# TT7B_v1_0.net
KiCad netlist of a schematic drawn in EAGLE
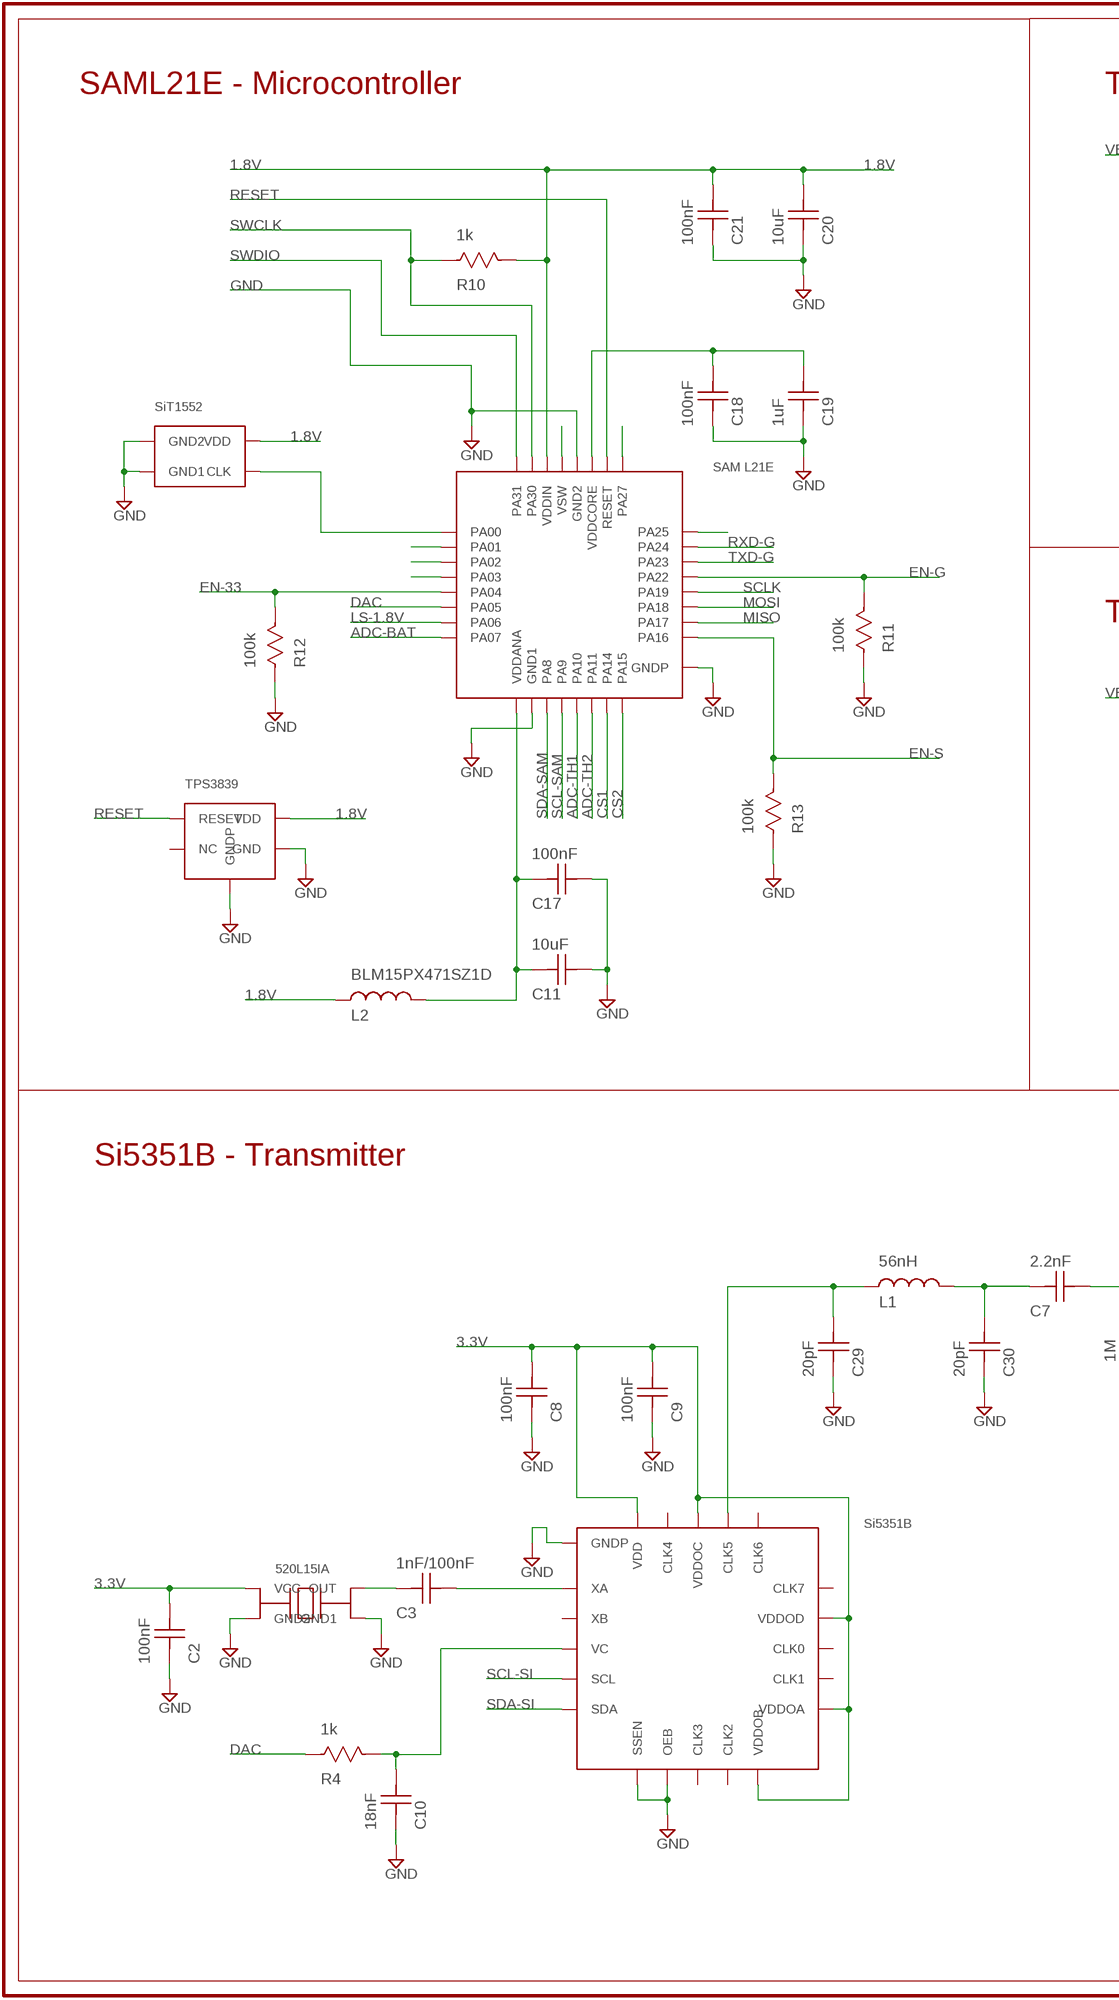
[diagram p0: schematic, sheet 1, part 1 of 2]
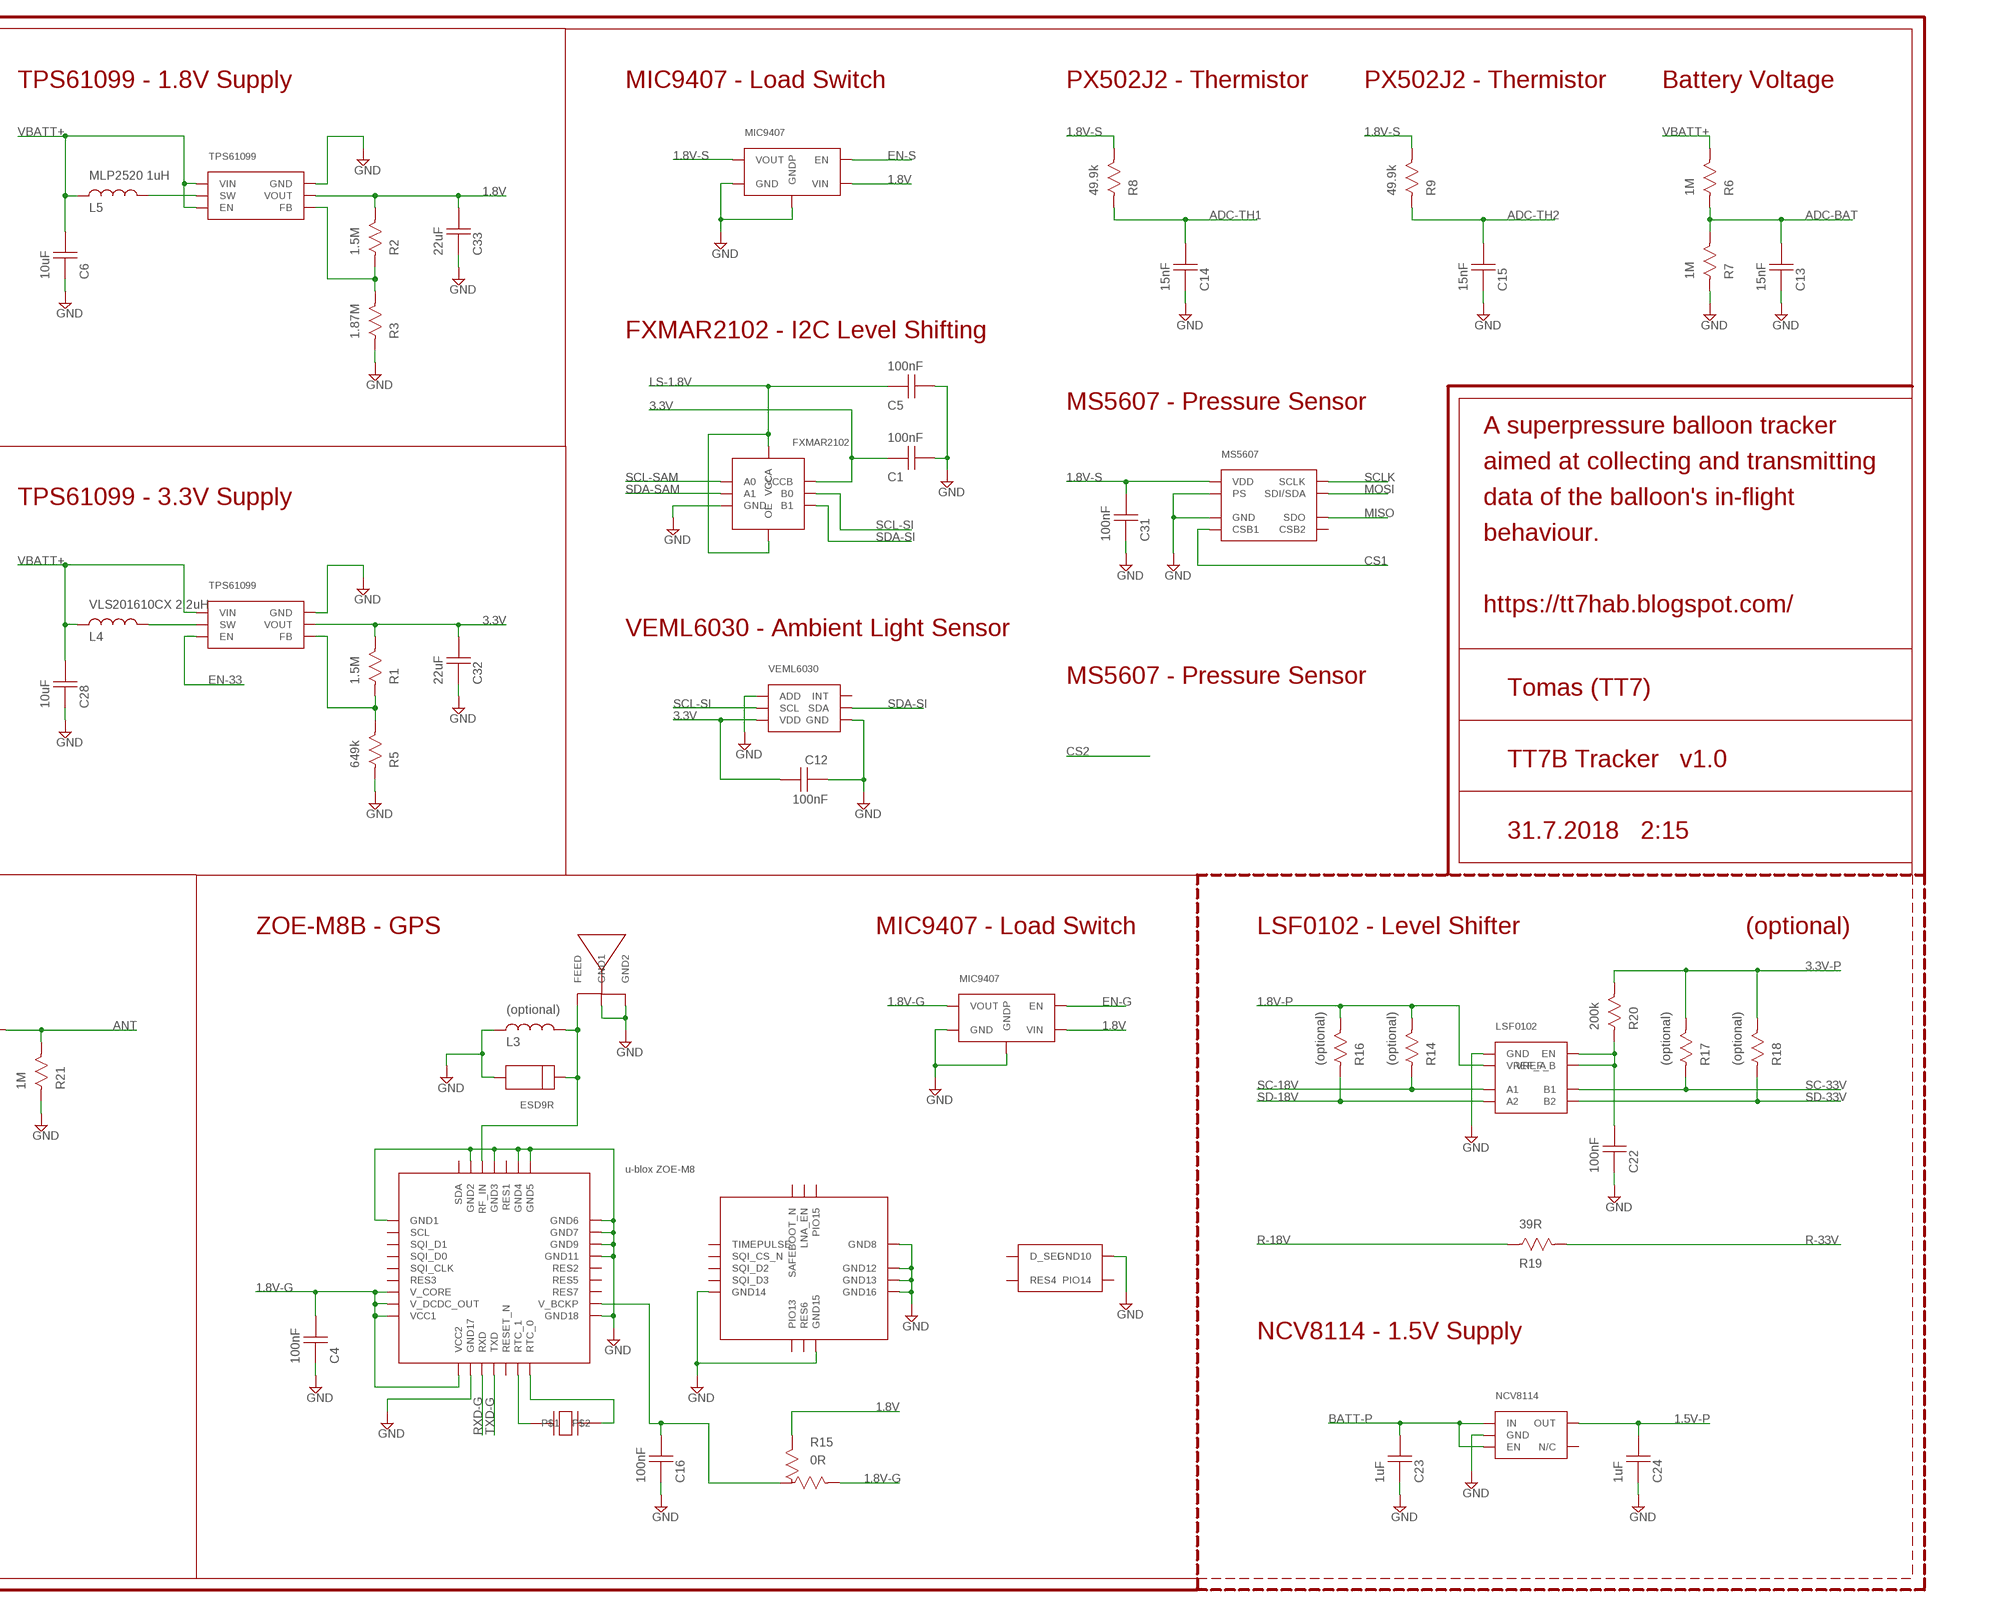
[diagram p1: schematic, sheet 1, part 2 of 2]

(export (version "E")
  (design (tool "Eeschema 10.0.6"))
  (components
    (comp (ref "C1")
      (value "100nF")
      (footprint "eagle-import:CAP0402")
      (libsource (lib "eagle-import") (part "CAP0402"))
    )
    (comp (ref "C2")
      (value "100nF")
      (footprint "eagle-import:CAP0402")
      (libsource (lib "eagle-import") (part "CAP0402"))
    )
    (comp (ref "C3")
      (value "1nF/100nF")
      (footprint "eagle-import:CAP0402")
      (libsource (lib "eagle-import") (part "CAP0402"))
    )
    (comp (ref "C4")
      (value "100nF")
      (footprint "eagle-import:CAP0402")
      (libsource (lib "eagle-import") (part "CAP0402"))
    )
    (comp (ref "C5")
      (value "100nF")
      (footprint "eagle-import:CAP0402")
      (libsource (lib "eagle-import") (part "CAP0402"))
    )
    (comp (ref "C6")
      (value "10uF")
      (footprint "eagle-import:CAP0402")
      (libsource (lib "eagle-import") (part "CAP0402"))
    )
    (comp (ref "C7")
      (value "2.2nF")
      (footprint "eagle-import:CAP0402")
      (libsource (lib "eagle-import") (part "CAP0402"))
    )
    (comp (ref "C8")
      (value "100nF")
      (footprint "eagle-import:CAP0402")
      (libsource (lib "eagle-import") (part "CAP0402"))
    )
    (comp (ref "C9")
      (value "100nF")
      (footprint "eagle-import:CAP0402")
      (libsource (lib "eagle-import") (part "CAP0402"))
    )
    (comp (ref "C10")
      (value "18nF")
      (footprint "eagle-import:CAP0402")
      (libsource (lib "eagle-import") (part "CAP0402"))
    )
    (comp (ref "C11")
      (value "10uF")
      (footprint "eagle-import:CAP0402")
      (libsource (lib "eagle-import") (part "CAP0402"))
    )
    (comp (ref "C12")
      (value "100nF")
      (footprint "eagle-import:CAP0402")
      (libsource (lib "eagle-import") (part "CAP0402"))
    )
    (comp (ref "C13")
      (value "15nF")
      (footprint "eagle-import:CAP0402")
      (libsource (lib "eagle-import") (part "CAP0402"))
    )
    (comp (ref "C14")
      (value "15nF")
      (footprint "eagle-import:CAP0402")
      (libsource (lib "eagle-import") (part "CAP0402"))
    )
    (comp (ref "C15")
      (value "15nF")
      (footprint "eagle-import:CAP0402")
      (libsource (lib "eagle-import") (part "CAP0402"))
    )
    (comp (ref "C16")
      (value "100nF")
      (footprint "eagle-import:CAP0402")
      (libsource (lib "eagle-import") (part "CAP0402"))
    )
    (comp (ref "C17")
      (value "100nF")
      (footprint "eagle-import:CAP0402")
      (libsource (lib "eagle-import") (part "CAP0402"))
    )
    (comp (ref "C18")
      (value "100nF")
      (footprint "eagle-import:CAP0402")
      (libsource (lib "eagle-import") (part "CAP0402"))
    )
    (comp (ref "C19")
      (value "1uF")
      (footprint "eagle-import:CAP0402")
      (libsource (lib "eagle-import") (part "CAP0402"))
    )
    (comp (ref "C20")
      (value "10uF")
      (footprint "eagle-import:CAP0402")
      (libsource (lib "eagle-import") (part "CAP0402"))
    )
    (comp (ref "C21")
      (value "100nF")
      (footprint "eagle-import:CAP0402")
      (libsource (lib "eagle-import") (part "CAP0402"))
    )
    (comp (ref "C22")
      (value "100nF")
      (footprint "eagle-import:CAP0402")
      (libsource (lib "eagle-import") (part "CAP0402"))
    )
    (comp (ref "C23")
      (value "1uF")
      (footprint "eagle-import:CAP0402")
      (libsource (lib "eagle-import") (part "CAP0402"))
    )
    (comp (ref "C24")
      (value "1uF")
      (footprint "eagle-import:CAP0402")
      (libsource (lib "eagle-import") (part "CAP0402"))
    )
    (comp (ref "C28")
      (value "10uF")
      (footprint "eagle-import:CAP0402")
      (libsource (lib "eagle-import") (part "CAP0402"))
    )
    (comp (ref "C29")
      (value "20pF")
      (footprint "eagle-import:CAP0402")
      (libsource (lib "eagle-import") (part "CAP0402"))
    )
    (comp (ref "C30")
      (value "20pF")
      (footprint "eagle-import:CAP0402")
      (libsource (lib "eagle-import") (part "CAP0402"))
    )
    (comp (ref "C31")
      (value "100nF")
      (footprint "eagle-import:CAP0402")
      (libsource (lib "eagle-import") (part "CAP0402"))
    )
    (comp (ref "C32")
      (value "22uF")
      (footprint "eagle-import:CAP0603")
      (libsource (lib "eagle-import") (part "CAP0603"))
    )
    (comp (ref "C33")
      (value "22uF")
      (footprint "eagle-import:CAP0603")
      (libsource (lib "eagle-import") (part "CAP0603"))
    )
    (comp (ref "D1")
      (value "ESD9R")
      (footprint "eagle-import:ESD9R")
      (libsource (lib "eagle-import") (part "ESD9R"))
    )
    (comp (ref "L1")
      (value "56nH")
      (footprint "eagle-import:IND0402")
      (libsource (lib "eagle-import") (part "IND0402"))
    )
    (comp (ref "L2")
      (value "BLM15PX471SZ1D")
      (footprint "eagle-import:IND0402")
      (libsource (lib "eagle-import") (part "IND0402"))
    )
    (comp (ref "L3")
      (value "(optional)")
      (footprint "eagle-import:IND0402")
      (libsource (lib "eagle-import") (part "IND0402"))
    )
    (comp (ref "L4")
      (value "VLS201610CX 2.2uH")
      (footprint "eagle-import:VLS201610CX")
      (libsource (lib "eagle-import") (part "VLS201610CX"))
    )
    (comp (ref "L5")
      (value "MLP2520 1uH")
      (footprint "eagle-import:MLP2520")
      (libsource (lib "eagle-import") (part "MLP2520"))
    )
    (comp (ref "R1")
      (value "1.5M")
      (footprint "eagle-import:RES0402")
      (libsource (lib "eagle-import") (part "RES0402"))
    )
    (comp (ref "R2")
      (value "1.5M")
      (footprint "eagle-import:RES0402")
      (libsource (lib "eagle-import") (part "RES0402"))
    )
    (comp (ref "R3")
      (value "1.87M")
      (footprint "eagle-import:RES0402")
      (libsource (lib "eagle-import") (part "RES0402"))
    )
    (comp (ref "R4")
      (value "1k")
      (footprint "eagle-import:RES0402")
      (libsource (lib "eagle-import") (part "RES0402"))
    )
    (comp (ref "R5")
      (value "649k")
      (footprint "eagle-import:RES0402")
      (libsource (lib "eagle-import") (part "RES0402"))
    )
    (comp (ref "R6")
      (value "1M")
      (footprint "eagle-import:RES0402")
      (libsource (lib "eagle-import") (part "RES0402"))
    )
    (comp (ref "R7")
      (value "1M")
      (footprint "eagle-import:RES0402")
      (libsource (lib "eagle-import") (part "RES0402"))
    )
    (comp (ref "R8")
      (value "49.9k")
      (footprint "eagle-import:RES0402")
      (libsource (lib "eagle-import") (part "RES0402"))
    )
    (comp (ref "R9")
      (value "49.9k")
      (footprint "eagle-import:RES0402")
      (libsource (lib "eagle-import") (part "RES0402"))
    )
    (comp (ref "R10")
      (value "1k")
      (footprint "eagle-import:RES0402")
      (libsource (lib "eagle-import") (part "RES0402"))
    )
    (comp (ref "R11")
      (value "100k")
      (footprint "eagle-import:RES0402")
      (libsource (lib "eagle-import") (part "RES0402"))
    )
    (comp (ref "R12")
      (value "100k")
      (footprint "eagle-import:RES0402")
      (libsource (lib "eagle-import") (part "RES0402"))
    )
    (comp (ref "R13")
      (value "100k")
      (footprint "eagle-import:RES0402")
      (libsource (lib "eagle-import") (part "RES0402"))
    )
    (comp (ref "R14")
      (value "(optional)")
      (footprint "eagle-import:RES0402")
      (libsource (lib "eagle-import") (part "RES0402"))
    )
    (comp (ref "R15")
      (value "0R")
      (footprint "eagle-import:RES0402-3")
      (libsource (lib "eagle-import") (part "RES0402-3"))
    )
    (comp (ref "R16")
      (value "(optional)")
      (footprint "eagle-import:RES0402")
      (libsource (lib "eagle-import") (part "RES0402"))
    )
    (comp (ref "R17")
      (value "(optional)")
      (footprint "eagle-import:RES0402")
      (libsource (lib "eagle-import") (part "RES0402"))
    )
    (comp (ref "R18")
      (value "(optional)")
      (footprint "eagle-import:RES0402")
      (libsource (lib "eagle-import") (part "RES0402"))
    )
    (comp (ref "R19")
      (value "39R")
      (footprint "eagle-import:RES0402")
      (libsource (lib "eagle-import") (part "RES0402"))
    )
    (comp (ref "R20")
      (value "200k")
      (footprint "eagle-import:RES0402")
      (libsource (lib "eagle-import") (part "RES0402"))
    )
    (comp (ref "R21")
      (value "1M")
      (footprint "eagle-import:RES0402")
      (libsource (lib "eagle-import") (part "RES0402"))
    )
    (comp (ref "U1")
      (value "SAML21E18B-MUT")
      (footprint "eagle-import:SAML21E18B-MUT")
      (libsource (lib "eagle-import") (part "SAML21E18B-MUT"))
    )
    (comp (ref "U2")
      (value "UBLOX_ZOE-M8")
      (footprint "eagle-import:UBLOX_ZOE-M8")
      (libsource (lib "eagle-import") (part "UBLOX_ZOE-M8"))
    )
    (comp (ref "U3")
      (value "FXMAR2102")
      (footprint "eagle-import:FXMAR2102")
      (libsource (lib "eagle-import") (part "FXMAR2102"))
    )
    (comp (ref "U4")
      (value "520L15IA")
      (footprint "eagle-import:520L15IA")
      (libsource (lib "eagle-import") (part "520L15IA"))
    )
    (comp (ref "U5")
      (value "CM8V-T1A")
      (footprint "eagle-import:CM8V-T1A")
      (libsource (lib "eagle-import") (part "CM8V-T1A"))
    )
    (comp (ref "U6")
      (value "MIC9407")
      (footprint "eagle-import:MIC9407")
      (libsource (lib "eagle-import") (part "MIC9407"))
    )
    (comp (ref "U7")
      (value "MS5607")
      (footprint "eagle-import:MS5607")
      (libsource (lib "eagle-import") (part "MS5607"))
    )
    (comp (ref "U8")
      (value "LSF0102")
      (footprint "eagle-import:LSF0102")
      (libsource (lib "eagle-import") (part "LSF0102"))
    )
    (comp (ref "U9")
      (value "NCV8114")
      (footprint "eagle-import:NCV8114")
      (libsource (lib "eagle-import") (part "NCV8114"))
    )
    (comp (ref "U10")
      (value "W3011A")
      (footprint "eagle-import:W3011A")
      (libsource (lib "eagle-import") (part "W3011A"))
    )
    (comp (ref "U11")
      (value "SI5351B")
      (footprint "eagle-import:SI5351B")
      (libsource (lib "eagle-import") (part "SI5351B"))
    )
    (comp (ref "U12")
      (value "TPS3839")
      (footprint "eagle-import:TPS383")
      (libsource (lib "eagle-import") (part "TPS3839"))
    )
    (comp (ref "U13")
      (value "MIC9407")
      (footprint "eagle-import:MIC9407")
      (libsource (lib "eagle-import") (part "MIC9407"))
    )
    (comp (ref "U14")
      (value "SIT1552")
      (footprint "eagle-import:SIT1552")
      (libsource (lib "eagle-import") (part "SIT1552"))
    )
    (comp (ref "U15")
      (value "VEML6030")
      (footprint "eagle-import:VEML6030")
      (libsource (lib "eagle-import") (part "VEML6030"))
    )
    (comp (ref "U16")
      (value "TPS61099")
      (footprint "eagle-import:TPS61099")
      (libsource (lib "eagle-import") (part "TPS61099"))
    )
    (comp (ref "U17")
      (value "TPS61099")
      (footprint "eagle-import:TPS61099")
      (libsource (lib "eagle-import") (part "TPS61099"))
    )
  )
  (nets
    (net (code "1") (name "/1.5V-P") (class "Default")
      (node (ref "C24") (pin "P$2") (pinfunction "P$2_P$2") (pintype "bidirectional"))
      (node (ref "U9") (pin "OUT") (pinfunction "OUT_OUT") (pintype "bidirectional"))
    )
    (net (code "2") (name "/1.8V") (class "Default")
      (node (ref "C20") (pin "P$2") (pinfunction "P$2_P$2") (pintype "bidirectional"))
      (node (ref "C21") (pin "P$2") (pinfunction "P$2_P$2") (pintype "bidirectional"))
      (node (ref "C33") (pin "P$2") (pinfunction "P$2_P$2") (pintype "bidirectional"))
      (node (ref "L2") (pin "P$1") (pinfunction "P$1_P$1") (pintype "bidirectional"))
      (node (ref "R10") (pin "P$2") (pinfunction "P$2_P$2") (pintype "bidirectional"))
      (node (ref "R15") (pin "1") (pinfunction "1_1") (pintype "bidirectional"))
      (node (ref "R2") (pin "P$2") (pinfunction "P$2_P$2") (pintype "bidirectional"))
      (node (ref "U1") (pin "VDDIN") (pinfunction "VDDIN_VDDIN") (pintype "bidirectional"))
      (node (ref "U12") (pin "VDD") (pinfunction "VDD_VDD") (pintype "bidirectional"))
      (node (ref "U13") (pin "VIN") (pinfunction "VIN_VIN") (pintype "bidirectional"))
      (node (ref "U14") (pin "VDD") (pinfunction "VDD_VDD") (pintype "bidirectional"))
      (node (ref "U16") (pin "VOUT") (pinfunction "VOUT_VOUT") (pintype "bidirectional"))
      (node (ref "U6") (pin "VIN") (pinfunction "VIN_VIN") (pintype "bidirectional"))
    )
    (net (code "3") (name "/1.8V-G") (class "Default")
      (node (ref "C4") (pin "P$2") (pinfunction "P$2_P$2") (pintype "bidirectional"))
      (node (ref "R15") (pin "3") (pinfunction "3_3") (pintype "bidirectional"))
      (node (ref "U2") (pin "VCC1") (pinfunction "VCC1_VCC1") (pintype "bidirectional"))
      (node (ref "U2") (pin "VCC2") (pinfunction "VCC2_VCC2") (pintype "bidirectional"))
      (node (ref "U2") (pin "V_CORE") (pinfunction "V_CORE_V_CORE") (pintype "bidirectional"))
      (node (ref "U2") (pin "V_DCDC_OUT") (pinfunction "V_DCDC_OUT_V_DCDC_OUT") (pintype "bidirectional"))
      (node (ref "U6") (pin "VOUT") (pinfunction "VOUT_VOUT") (pintype "bidirectional"))
    )
    (net (code "4") (name "/1.8V-P") (class "Default")
      (node (ref "R14") (pin "P$2") (pinfunction "P$2_P$2") (pintype "bidirectional"))
      (node (ref "R16") (pin "P$2") (pinfunction "P$2_P$2") (pintype "bidirectional"))
      (node (ref "U8") (pin "VREF_A") (pinfunction "VREF_A_VREF_A") (pintype "bidirectional"))
    )
    (net (code "5") (name "/1.8V-S") (class "Default")
      (node (ref "C31") (pin "P$2") (pinfunction "P$2_P$2") (pintype "bidirectional"))
      (node (ref "R8") (pin "P$2") (pinfunction "P$2_P$2") (pintype "bidirectional"))
      (node (ref "R9") (pin "P$2") (pinfunction "P$2_P$2") (pintype "bidirectional"))
      (node (ref "U13") (pin "VOUT") (pinfunction "VOUT_VOUT") (pintype "bidirectional"))
      (node (ref "U7") (pin "VDD") (pinfunction "VDD_VDD") (pintype "bidirectional"))
    )
    (net (code "6") (name "/3.3V") (class "Default")
      (node (ref "C1") (pin "P$1") (pinfunction "P$1_P$1") (pintype "bidirectional"))
      (node (ref "C12") (pin "P$2") (pinfunction "P$2_P$2") (pintype "bidirectional"))
      (node (ref "C2") (pin "P$2") (pinfunction "P$2_P$2") (pintype "bidirectional"))
      (node (ref "C32") (pin "P$2") (pinfunction "P$2_P$2") (pintype "bidirectional"))
      (node (ref "C8") (pin "P$2") (pinfunction "P$2_P$2") (pintype "bidirectional"))
      (node (ref "C9") (pin "P$2") (pinfunction "P$2_P$2") (pintype "bidirectional"))
      (node (ref "R1") (pin "P$2") (pinfunction "P$2_P$2") (pintype "bidirectional"))
      (node (ref "U11") (pin "VDD") (pinfunction "VDD_VDD") (pintype "bidirectional"))
      (node (ref "U11") (pin "VDDOA") (pinfunction "VDDOA_VDDOA") (pintype "bidirectional"))
      (node (ref "U11") (pin "VDDOB") (pinfunction "VDDOB_VDDOB") (pintype "bidirectional"))
      (node (ref "U11") (pin "VDDOC") (pinfunction "VDDOC_VDDOC") (pintype "bidirectional"))
      (node (ref "U11") (pin "VDDOD") (pinfunction "VDDOD_VDDOD") (pintype "bidirectional"))
      (node (ref "U15") (pin "VDD") (pinfunction "VDD_VDD") (pintype "bidirectional"))
      (node (ref "U17") (pin "VOUT") (pinfunction "VOUT_VOUT") (pintype "bidirectional"))
      (node (ref "U3") (pin "VCCB") (pinfunction "VCCB_VCCB") (pintype "bidirectional"))
      (node (ref "U4") (pin "VCC") (pinfunction "VCC_VCC") (pintype "bidirectional"))
    )
    (net (code "7") (name "/3.3V-P") (class "Default")
      (node (ref "R17") (pin "P$2") (pinfunction "P$2_P$2") (pintype "bidirectional"))
      (node (ref "R18") (pin "P$2") (pinfunction "P$2_P$2") (pintype "bidirectional"))
      (node (ref "R20") (pin "P$2") (pinfunction "P$2_P$2") (pintype "bidirectional"))
    )
    (net (code "8") (name "/ADC-BAT") (class "Default")
      (node (ref "C13") (pin "P$2") (pinfunction "P$2_P$2") (pintype "bidirectional"))
      (node (ref "R6") (pin "P$1") (pinfunction "P$1_P$1") (pintype "bidirectional"))
      (node (ref "R7") (pin "P$2") (pinfunction "P$2_P$2") (pintype "bidirectional"))
      (node (ref "U1") (pin "PA07") (pinfunction "PA07_PA07") (pintype "bidirectional"))
    )
    (net (code "9") (name "/ADC-TH1") (class "Default")
      (node (ref "C14") (pin "P$2") (pinfunction "P$2_P$2") (pintype "bidirectional"))
      (node (ref "R8") (pin "P$1") (pinfunction "P$1_P$1") (pintype "bidirectional"))
      (node (ref "U1") (pin "PA10") (pinfunction "PA10_PA10") (pintype "bidirectional"))
    )
    (net (code "10") (name "/ADC-TH2") (class "Default")
      (node (ref "C15") (pin "P$2") (pinfunction "P$2_P$2") (pintype "bidirectional"))
      (node (ref "R9") (pin "P$1") (pinfunction "P$1_P$1") (pintype "bidirectional"))
      (node (ref "U1") (pin "PA11") (pinfunction "PA11_PA11") (pintype "bidirectional"))
    )
    (net (code "11") (name "/ANT") (class "Default")
      (node (ref "C7") (pin "P$2") (pinfunction "P$2_P$2") (pintype "bidirectional"))
      (node (ref "R21") (pin "P$2") (pinfunction "P$2_P$2") (pintype "bidirectional"))
    )
    (net (code "12") (name "/BATT-P") (class "Default")
      (node (ref "C23") (pin "P$2") (pinfunction "P$2_P$2") (pintype "bidirectional"))
      (node (ref "U9") (pin "EN") (pinfunction "EN_EN") (pintype "bidirectional"))
      (node (ref "U9") (pin "IN") (pinfunction "IN_IN") (pintype "bidirectional"))
    )
    (net (code "13") (name "/CS1") (class "Default")
      (node (ref "U1") (pin "PA14") (pinfunction "PA14_PA14") (pintype "bidirectional"))
      (node (ref "U7") (pin "CSB1") (pinfunction "CSB1_CSB1") (pintype "bidirectional"))
    )
    (net (code "14") (name "/CS2") (class "Default")
      (node (ref "U1") (pin "PA15") (pinfunction "PA15_PA15") (pintype "bidirectional"))
    )
    (net (code "15") (name "/DAC") (class "Default")
      (node (ref "R4") (pin "P$1") (pinfunction "P$1_P$1") (pintype "bidirectional"))
      (node (ref "U1") (pin "PA05") (pinfunction "PA05_PA05") (pintype "bidirectional"))
    )
    (net (code "16") (name "/EN-33") (class "Default")
      (node (ref "R12") (pin "P$2") (pinfunction "P$2_P$2") (pintype "bidirectional"))
      (node (ref "U1") (pin "PA04") (pinfunction "PA04_PA04") (pintype "bidirectional"))
      (node (ref "U17") (pin "EN") (pinfunction "EN_EN") (pintype "bidirectional"))
    )
    (net (code "17") (name "/EN-G") (class "Default")
      (node (ref "R11") (pin "P$2") (pinfunction "P$2_P$2") (pintype "bidirectional"))
      (node (ref "U1") (pin "PA22") (pinfunction "PA22_PA22") (pintype "bidirectional"))
      (node (ref "U6") (pin "EN") (pinfunction "EN_EN") (pintype "bidirectional"))
    )
    (net (code "18") (name "/EN-S") (class "Default")
      (node (ref "R13") (pin "P$2") (pinfunction "P$2_P$2") (pintype "bidirectional"))
      (node (ref "U1") (pin "PA16") (pinfunction "PA16_PA16") (pintype "bidirectional"))
      (node (ref "U13") (pin "EN") (pinfunction "EN_EN") (pintype "bidirectional"))
    )
    (net (code "19") (name "/LS-1.8V") (class "Default")
      (node (ref "C5") (pin "P$1") (pinfunction "P$1_P$1") (pintype "bidirectional"))
      (node (ref "U1") (pin "PA06") (pinfunction "PA06_PA06") (pintype "bidirectional"))
      (node (ref "U3") (pin "OE") (pinfunction "OE_OE") (pintype "bidirectional"))
      (node (ref "U3") (pin "VCCA") (pinfunction "VCCA_VCCA") (pintype "bidirectional"))
    )
    (net (code "20") (name "/MISO") (class "Default")
      (node (ref "U1") (pin "PA17") (pinfunction "PA17_PA17") (pintype "bidirectional"))
      (node (ref "U7") (pin "SDO") (pinfunction "SDO_SDO") (pintype "bidirectional"))
    )
    (net (code "21") (name "/MOSI") (class "Default")
      (node (ref "U1") (pin "PA18") (pinfunction "PA18_PA18") (pintype "bidirectional"))
      (node (ref "U7") (pin "SDI/SDA") (pinfunction "SDI/SDA_SDI/SDA") (pintype "bidirectional"))
    )
    (net (code "22") (name "/R-18V") (class "Default")
      (node (ref "R19") (pin "P$1") (pinfunction "P$1_P$1") (pintype "bidirectional"))
    )
    (net (code "23") (name "/R-33V") (class "Default")
      (node (ref "R19") (pin "P$2") (pinfunction "P$2_P$2") (pintype "bidirectional"))
    )
    (net (code "24") (name "/RESET") (class "Default")
      (node (ref "U1") (pin "RESET") (pinfunction "RESET_RESET") (pintype "bidirectional"))
      (node (ref "U12") (pin "RESET") (pinfunction "RESET_RESET") (pintype "bidirectional"))
    )
    (net (code "25") (name "/RXD-G") (class "Default")
      (node (ref "U1") (pin "PA24") (pinfunction "PA24_PA24") (pintype "bidirectional"))
      (node (ref "U2") (pin "RXD") (pinfunction "RXD_RXD") (pintype "bidirectional"))
    )
    (net (code "26") (name "/SC-18V") (class "Default")
      (node (ref "R14") (pin "P$1") (pinfunction "P$1_P$1") (pintype "bidirectional"))
      (node (ref "U8") (pin "A1") (pinfunction "A1_A1") (pintype "bidirectional"))
    )
    (net (code "27") (name "/SC-33V") (class "Default")
      (node (ref "R17") (pin "P$1") (pinfunction "P$1_P$1") (pintype "bidirectional"))
      (node (ref "U8") (pin "B1") (pinfunction "B1_B1") (pintype "bidirectional"))
    )
    (net (code "28") (name "/SCL-SAM") (class "Default")
      (node (ref "U1") (pin "PA09") (pinfunction "PA9_PA09") (pintype "bidirectional"))
      (node (ref "U3") (pin "A0") (pinfunction "A0_A0") (pintype "bidirectional"))
    )
    (net (code "29") (name "/SCL-SI") (class "Default")
      (node (ref "U11") (pin "SCL") (pinfunction "SCL_SCL") (pintype "bidirectional"))
      (node (ref "U15") (pin "SCL") (pinfunction "SCL_SCL") (pintype "bidirectional"))
      (node (ref "U3") (pin "B0") (pinfunction "B0_B0") (pintype "bidirectional"))
    )
    (net (code "30") (name "/SCLK") (class "Default")
      (node (ref "U1") (pin "PA19") (pinfunction "PA19_PA19") (pintype "bidirectional"))
      (node (ref "U7") (pin "SCLK") (pinfunction "SCLK_SCLK") (pintype "bidirectional"))
    )
    (net (code "31") (name "/SD-18V") (class "Default")
      (node (ref "R16") (pin "P$1") (pinfunction "P$1_P$1") (pintype "bidirectional"))
      (node (ref "U8") (pin "A2") (pinfunction "A2_A2") (pintype "bidirectional"))
    )
    (net (code "32") (name "/SD-33V") (class "Default")
      (node (ref "R18") (pin "P$1") (pinfunction "P$1_P$1") (pintype "bidirectional"))
      (node (ref "U8") (pin "B2") (pinfunction "B2_B2") (pintype "bidirectional"))
    )
    (net (code "33") (name "/SDA-SAM") (class "Default")
      (node (ref "U1") (pin "PA08") (pinfunction "PA8_PA08") (pintype "bidirectional"))
      (node (ref "U3") (pin "A1") (pinfunction "A1_A1") (pintype "bidirectional"))
    )
    (net (code "34") (name "/SDA-SI") (class "Default")
      (node (ref "U11") (pin "SDA") (pinfunction "SDA_SDA") (pintype "bidirectional"))
      (node (ref "U15") (pin "SDA") (pinfunction "SDA_SDA") (pintype "bidirectional"))
      (node (ref "U3") (pin "B1") (pinfunction "B1_B1") (pintype "bidirectional"))
    )
    (net (code "35") (name "/SWCLK") (class "Default")
      (node (ref "R10") (pin "P$1") (pinfunction "P$1_P$1") (pintype "bidirectional"))
      (node (ref "U1") (pin "PA30") (pinfunction "PA30_PA30") (pintype "bidirectional"))
    )
    (net (code "36") (name "/SWDIO") (class "Default")
      (node (ref "U1") (pin "PA31") (pinfunction "PA31_PA31") (pintype "bidirectional"))
    )
    (net (code "37") (name "/TXD-G") (class "Default")
      (node (ref "U1") (pin "PA23") (pinfunction "PA23_PA23") (pintype "bidirectional"))
      (node (ref "U2") (pin "TXD") (pinfunction "TXD_TXD") (pintype "bidirectional"))
    )
    (net (code "38") (name "/VBATT+") (class "Default")
      (node (ref "C28") (pin "P$2") (pinfunction "P$2_P$2") (pintype "bidirectional"))
      (node (ref "C6") (pin "P$2") (pinfunction "P$2_P$2") (pintype "bidirectional"))
      (node (ref "L4") (pin "P$1") (pinfunction "P$1_P$1") (pintype "bidirectional"))
      (node (ref "L5") (pin "P$1") (pinfunction "P$1_P$1") (pintype "bidirectional"))
      (node (ref "R6") (pin "P$2") (pinfunction "P$2_P$2") (pintype "bidirectional"))
      (node (ref "U16") (pin "EN") (pinfunction "EN_EN") (pintype "bidirectional"))
      (node (ref "U16") (pin "VIN") (pinfunction "VIN_VIN") (pintype "bidirectional"))
      (node (ref "U17") (pin "VIN") (pinfunction "VIN_VIN") (pintype "bidirectional"))
    )
    (net (code "39") (name "GND") (class "Default")
      (node (ref "C1") (pin "P$2") (pinfunction "P$2_P$2") (pintype "bidirectional"))
      (node (ref "C10") (pin "P$1") (pinfunction "P$1_P$1") (pintype "bidirectional"))
      (node (ref "C11") (pin "P$2") (pinfunction "P$2_P$2") (pintype "bidirectional"))
      (node (ref "C12") (pin "P$1") (pinfunction "P$1_P$1") (pintype "bidirectional"))
      (node (ref "C13") (pin "P$1") (pinfunction "P$1_P$1") (pintype "bidirectional"))
      (node (ref "C14") (pin "P$1") (pinfunction "P$1_P$1") (pintype "bidirectional"))
      (node (ref "C15") (pin "P$1") (pinfunction "P$1_P$1") (pintype "bidirectional"))
      (node (ref "C16") (pin "P$1") (pinfunction "P$1_P$1") (pintype "bidirectional"))
      (node (ref "C17") (pin "P$2") (pinfunction "P$2_P$2") (pintype "bidirectional"))
      (node (ref "C18") (pin "P$1") (pinfunction "P$1_P$1") (pintype "bidirectional"))
      (node (ref "C19") (pin "P$1") (pinfunction "P$1_P$1") (pintype "bidirectional"))
      (node (ref "C2") (pin "P$1") (pinfunction "P$1_P$1") (pintype "bidirectional"))
      (node (ref "C20") (pin "P$1") (pinfunction "P$1_P$1") (pintype "bidirectional"))
      (node (ref "C21") (pin "P$1") (pinfunction "P$1_P$1") (pintype "bidirectional"))
      (node (ref "C22") (pin "P$1") (pinfunction "P$1_P$1") (pintype "bidirectional"))
      (node (ref "C23") (pin "P$1") (pinfunction "P$1_P$1") (pintype "bidirectional"))
      (node (ref "C24") (pin "P$1") (pinfunction "P$1_P$1") (pintype "bidirectional"))
      (node (ref "C28") (pin "P$1") (pinfunction "P$1_P$1") (pintype "bidirectional"))
      (node (ref "C29") (pin "P$1") (pinfunction "P$1_P$1") (pintype "bidirectional"))
      (node (ref "C30") (pin "P$1") (pinfunction "P$1_P$1") (pintype "bidirectional"))
      (node (ref "C31") (pin "P$1") (pinfunction "P$1_P$1") (pintype "bidirectional"))
      (node (ref "C32") (pin "P$1") (pinfunction "P$1_P$1") (pintype "bidirectional"))
      (node (ref "C33") (pin "P$1") (pinfunction "P$1_P$1") (pintype "bidirectional"))
      (node (ref "C4") (pin "P$1") (pinfunction "P$1_P$1") (pintype "bidirectional"))
      (node (ref "C5") (pin "P$2") (pinfunction "P$2_P$2") (pintype "bidirectional"))
      (node (ref "C6") (pin "P$1") (pinfunction "P$1_P$1") (pintype "bidirectional"))
      (node (ref "C8") (pin "P$1") (pinfunction "P$1_P$1") (pintype "bidirectional"))
      (node (ref "C9") (pin "P$1") (pinfunction "P$1_P$1") (pintype "bidirectional"))
      (node (ref "D1") (pin "2") (pinfunction "2_2") (pintype "bidirectional"))
      (node (ref "L3") (pin "P$1") (pinfunction "P$1_P$1") (pintype "bidirectional"))
      (node (ref "R11") (pin "P$1") (pinfunction "P$1_P$1") (pintype "bidirectional"))
      (node (ref "R12") (pin "P$1") (pinfunction "P$1_P$1") (pintype "bidirectional"))
      (node (ref "R13") (pin "P$1") (pinfunction "P$1_P$1") (pintype "bidirectional"))
      (node (ref "R21") (pin "P$1") (pinfunction "P$1_P$1") (pintype "bidirectional"))
      (node (ref "R3") (pin "P$1") (pinfunction "P$1_P$1") (pintype "bidirectional"))
      (node (ref "R5") (pin "P$1") (pinfunction "P$1_P$1") (pintype "bidirectional"))
      (node (ref "R7") (pin "P$1") (pinfunction "P$1_P$1") (pintype "bidirectional"))
      (node (ref "U1") (pin "GND1") (pinfunction "GND1_GND1") (pintype "bidirectional"))
      (node (ref "U1") (pin "GND2") (pinfunction "GND2_GND2") (pintype "bidirectional"))
      (node (ref "U1") (pin "GNDP") (pinfunction "GNDP_GNDP") (pintype "bidirectional"))
      (node (ref "U10") (pin "GND1") (pinfunction "GND1_GND1") (pintype "bidirectional"))
      (node (ref "U10") (pin "GND2") (pinfunction "GND2_GND2") (pintype "bidirectional"))
      (node (ref "U11") (pin "GNDP") (pinfunction "GNDP_GNDP") (pintype "bidirectional"))
      (node (ref "U11") (pin "OEB") (pinfunction "OEB_OEB") (pintype "bidirectional"))
      (node (ref "U11") (pin "SSEN") (pinfunction "SSEN_SSEN") (pintype "bidirectional"))
      (node (ref "U12") (pin "GND") (pinfunction "GND_GND") (pintype "bidirectional"))
      (node (ref "U12") (pin "GNDP") (pinfunction "GNDP_GNDP") (pintype "bidirectional"))
      (node (ref "U13") (pin "GND") (pinfunction "GND_GND") (pintype "bidirectional"))
      (node (ref "U13") (pin "GNDP") (pinfunction "GNDP_GNDP") (pintype "bidirectional"))
      (node (ref "U14") (pin "GND1") (pinfunction "GND1_GND1") (pintype "bidirectional"))
      (node (ref "U14") (pin "GND2") (pinfunction "GND2_GND2") (pintype "bidirectional"))
      (node (ref "U15") (pin "ADD") (pinfunction "ADD_ADD") (pintype "bidirectional"))
      (node (ref "U15") (pin "GND") (pinfunction "GND_GND") (pintype "bidirectional"))
      (node (ref "U16") (pin "GND") (pinfunction "GND_GND") (pintype "bidirectional"))
      (node (ref "U17") (pin "GND") (pinfunction "GND_GND") (pintype "bidirectional"))
      (node (ref "U2") (pin "GND1") (pinfunction "GND1_GND1") (pintype "bidirectional"))
      (node (ref "U2") (pin "GND10") (pinfunction "GND10_GND10") (pintype "bidirectional"))
      (node (ref "U2") (pin "GND11") (pinfunction "GND11_GND11") (pintype "bidirectional"))
      (node (ref "U2") (pin "GND12") (pinfunction "GND12_GND12") (pintype "bidirectional"))
      (node (ref "U2") (pin "GND13") (pinfunction "GND13_GND13") (pintype "bidirectional"))
      (node (ref "U2") (pin "GND14") (pinfunction "GND14_GND14") (pintype "bidirectional"))
      (node (ref "U2") (pin "GND15") (pinfunction "GND15_GND15") (pintype "bidirectional"))
      (node (ref "U2") (pin "GND16") (pinfunction "GND16_GND16") (pintype "bidirectional"))
      (node (ref "U2") (pin "GND17") (pinfunction "GND17_GND17") (pintype "bidirectional"))
      (node (ref "U2") (pin "GND18") (pinfunction "GND18_GND18") (pintype "bidirectional"))
      (node (ref "U2") (pin "GND2") (pinfunction "GND2_GND2") (pintype "bidirectional"))
      (node (ref "U2") (pin "GND3") (pinfunction "GND3_GND3") (pintype "bidirectional"))
      (node (ref "U2") (pin "GND4") (pinfunction "GND4_GND4") (pintype "bidirectional"))
      (node (ref "U2") (pin "GND5") (pinfunction "GND5_GND5") (pintype "bidirectional"))
      (node (ref "U2") (pin "GND6") (pinfunction "GND6_GND6") (pintype "bidirectional"))
      (node (ref "U2") (pin "GND7") (pinfunction "GND7_GND7") (pintype "bidirectional"))
      (node (ref "U2") (pin "GND8") (pinfunction "GND8_GND8") (pintype "bidirectional"))
      (node (ref "U2") (pin "GND9") (pinfunction "GND9_GND9") (pintype "bidirectional"))
      (node (ref "U3") (pin "GND") (pinfunction "GND_GND") (pintype "bidirectional"))
      (node (ref "U4") (pin "GND1") (pinfunction "GND1_GND1") (pintype "bidirectional"))
      (node (ref "U4") (pin "GND2") (pinfunction "GND2_GND2") (pintype "bidirectional"))
      (node (ref "U6") (pin "GND") (pinfunction "GND_GND") (pintype "bidirectional"))
      (node (ref "U6") (pin "GNDP") (pinfunction "GNDP_GNDP") (pintype "bidirectional"))
      (node (ref "U7") (pin "GND") (pinfunction "GND_GND") (pintype "bidirectional"))
      (node (ref "U7") (pin "PS") (pinfunction "PS_PS") (pintype "bidirectional"))
      (node (ref "U8") (pin "GND") (pinfunction "GND_GND") (pintype "bidirectional"))
      (node (ref "U9") (pin "GND") (pinfunction "GND_GND") (pintype "bidirectional"))
    )
    (net (code "40") (name "Net-(C3-PadP$1)") (class "Default")
      (node (ref "C3") (pin "P$1") (pinfunction "P$1_P$1") (pintype "bidirectional"))
      (node (ref "U4") (pin "OUT") (pinfunction "OUT_OUT") (pintype "bidirectional"))
    )
    (net (code "41") (name "Net-(C3-PadP$2)") (class "Default")
      (node (ref "C3") (pin "P$2") (pinfunction "P$2_P$2") (pintype "bidirectional"))
      (node (ref "U11") (pin "XA") (pinfunction "XA_XA") (pintype "bidirectional"))
    )
    (net (code "42") (name "Net-(C10-PadP$2)") (class "Default")
      (node (ref "C10") (pin "P$2") (pinfunction "P$2_P$2") (pintype "bidirectional"))
      (node (ref "R4") (pin "P$2") (pinfunction "P$2_P$2") (pintype "bidirectional"))
      (node (ref "U11") (pin "VC") (pinfunction "VC_VC") (pintype "bidirectional"))
    )
    (net (code "43") (name "Net-(C11-PadP$1)") (class "Default")
      (node (ref "C11") (pin "P$1") (pinfunction "P$1_P$1") (pintype "bidirectional"))
      (node (ref "C17") (pin "P$1") (pinfunction "P$1_P$1") (pintype "bidirectional"))
      (node (ref "L2") (pin "P$2") (pinfunction "P$2_P$2") (pintype "bidirectional"))
      (node (ref "U1") (pin "VDDANA") (pinfunction "VDDANA_VDDANA") (pintype "bidirectional"))
    )
    (net (code "44") (name "Net-(C16-PadP$2)") (class "Default")
      (node (ref "C16") (pin "P$2") (pinfunction "P$2_P$2") (pintype "bidirectional"))
      (node (ref "R15") (pin "2") (pinfunction "2_2") (pintype "bidirectional"))
      (node (ref "U2") (pin "V_BCKP") (pinfunction "V_BCKP_V_BCKP") (pintype "bidirectional"))
    )
    (net (code "45") (name "Net-(C18-PadP$2)") (class "Default")
      (node (ref "C18") (pin "P$2") (pinfunction "P$2_P$2") (pintype "bidirectional"))
      (node (ref "C19") (pin "P$2") (pinfunction "P$2_P$2") (pintype "bidirectional"))
      (node (ref "U1") (pin "VDDCORE") (pinfunction "VDDCORE_VDDCORE") (pintype "bidirectional"))
    )
    (net (code "46") (name "Net-(C22-PadP$2)") (class "Default")
      (node (ref "C22") (pin "P$2") (pinfunction "P$2_P$2") (pintype "bidirectional"))
      (node (ref "R20") (pin "P$1") (pinfunction "P$1_P$1") (pintype "bidirectional"))
      (node (ref "U8") (pin "EN") (pinfunction "EN_EN") (pintype "bidirectional"))
      (node (ref "U8") (pin "VREF_B") (pinfunction "VREF_B_VREF_B") (pintype "bidirectional"))
    )
    (net (code "47") (name "Net-(C29-PadP$2)") (class "Default")
      (node (ref "C29") (pin "P$2") (pinfunction "P$2_P$2") (pintype "bidirectional"))
      (node (ref "L1") (pin "P$1") (pinfunction "P$1_P$1") (pintype "bidirectional"))
      (node (ref "U11") (pin "CLK5") (pinfunction "CLK5_CLK5") (pintype "bidirectional"))
    )
    (net (code "48") (name "Net-(C30-PadP$2)") (class "Default")
      (node (ref "C30") (pin "P$2") (pinfunction "P$2_P$2") (pintype "bidirectional"))
      (node (ref "C7") (pin "P$1") (pinfunction "P$1_P$1") (pintype "bidirectional"))
      (node (ref "L1") (pin "P$2") (pinfunction "P$2_P$2") (pintype "bidirectional"))
    )
    (net (code "49") (name "Net-(D1-Pad1)") (class "Default")
      (node (ref "D1") (pin "1") (pinfunction "1_1") (pintype "bidirectional"))
      (node (ref "L3") (pin "P$2") (pinfunction "P$2_P$2") (pintype "bidirectional"))
      (node (ref "U10") (pin "FEED") (pinfunction "FEED_FEED") (pintype "bidirectional"))
      (node (ref "U2") (pin "RF_IN") (pinfunction "RF_IN_RF_IN") (pintype "bidirectional"))
    )
    (net (code "50") (name "Net-(L4-PadP$2)") (class "Default")
      (node (ref "L4") (pin "P$2") (pinfunction "P$2_P$2") (pintype "bidirectional"))
      (node (ref "U17") (pin "SW") (pinfunction "SW_SW") (pintype "bidirectional"))
    )
    (net (code "51") (name "Net-(L5-PadP$2)") (class "Default")
      (node (ref "L5") (pin "P$2") (pinfunction "P$2_P$2") (pintype "bidirectional"))
      (node (ref "U16") (pin "SW") (pinfunction "SW_SW") (pintype "bidirectional"))
    )
    (net (code "52") (name "Net-(R1-PadP$1)") (class "Default")
      (node (ref "R1") (pin "P$1") (pinfunction "P$1_P$1") (pintype "bidirectional"))
      (node (ref "R5") (pin "P$2") (pinfunction "P$2_P$2") (pintype "bidirectional"))
      (node (ref "U17") (pin "FB") (pinfunction "FB_FB") (pintype "bidirectional"))
    )
    (net (code "53") (name "Net-(R2-PadP$1)") (class "Default")
      (node (ref "R2") (pin "P$1") (pinfunction "P$1_P$1") (pintype "bidirectional"))
      (node (ref "R3") (pin "P$2") (pinfunction "P$2_P$2") (pintype "bidirectional"))
      (node (ref "U16") (pin "FB") (pinfunction "FB_FB") (pintype "bidirectional"))
    )
    (net (code "54") (name "Net-(U1-PadPA00)") (class "Default")
      (node (ref "U1") (pin "PA00") (pinfunction "PA00_PA00") (pintype "bidirectional"))
      (node (ref "U14") (pin "CLK") (pinfunction "CLK_CLK") (pintype "bidirectional"))
    )
    (net (code "55") (name "Net-(U2-PadRTC_0)") (class "Default")
      (node (ref "U2") (pin "RTC_0") (pinfunction "RTC_0_RTC_0") (pintype "bidirectional"))
      (node (ref "U5") (pin "P$2") (pinfunction "P$2_P$2") (pintype "bidirectional"))
    )
    (net (code "56") (name "Net-(U2-PadRTC_1)") (class "Default")
      (node (ref "U2") (pin "RTC_1") (pinfunction "RTC_1_RTC_1") (pintype "bidirectional"))
      (node (ref "U5") (pin "P$1") (pinfunction "P$1_P$1") (pintype "bidirectional"))
    )
    (net (code "57") (name "unconnected-(U1-PadPA01)") (class "Default")
      (node (ref "U1") (pin "PA01") (pinfunction "PA01_PA01") (pintype "bidirectional"))
    )
    (net (code "58") (name "unconnected-(U1-PadPA02)") (class "Default")
      (node (ref "U1") (pin "PA02") (pinfunction "PA02_PA02") (pintype "bidirectional"))
    )
    (net (code "59") (name "unconnected-(U1-PadPA03)") (class "Default")
      (node (ref "U1") (pin "PA03") (pinfunction "PA03_PA03") (pintype "bidirectional"))
    )
    (net (code "60") (name "unconnected-(U1-PadPA25)") (class "Default")
      (node (ref "U1") (pin "PA25") (pinfunction "PA25_PA25") (pintype "bidirectional"))
    )
    (net (code "61") (name "unconnected-(U1-PadPA27)") (class "Default")
      (node (ref "U1") (pin "PA27") (pinfunction "PA27_PA27") (pintype "bidirectional"))
    )
    (net (code "62") (name "unconnected-(U1-PadVSW)") (class "Default")
      (node (ref "U1") (pin "VSW") (pinfunction "VSW_VSW") (pintype "bidirectional"))
    )
    (net (code "63") (name "unconnected-(U2-PadD_SEL)") (class "Default")
      (node (ref "U2") (pin "D_SEL") (pinfunction "D_SEL_D_SEL") (pintype "bidirectional"))
    )
    (net (code "64") (name "unconnected-(U2-PadLNA_EN)") (class "Default")
      (node (ref "U2") (pin "LNA_EN") (pinfunction "LNA_EN_LNA_EN") (pintype "bidirectional"))
    )
    (net (code "65") (name "unconnected-(U2-PadPIO13)") (class "Default")
      (node (ref "U2") (pin "PIO13") (pinfunction "PIO13_PIO13") (pintype "bidirectional"))
    )
    (net (code "66") (name "unconnected-(U2-PadPIO14)") (class "Default")
      (node (ref "U2") (pin "PIO14") (pinfunction "PIO14_PIO14") (pintype "bidirectional"))
    )
    (net (code "67") (name "unconnected-(U2-PadPIO15)") (class "Default")
      (node (ref "U2") (pin "PIO15") (pinfunction "PIO15_PIO15") (pintype "bidirectional"))
    )
    (net (code "68") (name "unconnected-(U2-PadRES1)") (class "Default")
      (node (ref "U2") (pin "RES1") (pinfunction "RES1_RES1") (pintype "bidirectional"))
    )
    (net (code "69") (name "unconnected-(U2-PadRES2)") (class "Default")
      (node (ref "U2") (pin "RES2") (pinfunction "RES2_RES2") (pintype "bidirectional"))
    )
    (net (code "70") (name "unconnected-(U2-PadRES3)") (class "Default")
      (node (ref "U2") (pin "RES3") (pinfunction "RES3_RES3") (pintype "bidirectional"))
    )
    (net (code "71") (name "unconnected-(U2-PadRES4)") (class "Default")
      (node (ref "U2") (pin "RES4") (pinfunction "RES4_RES4") (pintype "bidirectional"))
    )
    (net (code "72") (name "unconnected-(U2-PadRES5)") (class "Default")
      (node (ref "U2") (pin "RES5") (pinfunction "RES5_RES5") (pintype "bidirectional"))
    )
    (net (code "73") (name "unconnected-(U2-PadRES6)") (class "Default")
      (node (ref "U2") (pin "RES6") (pinfunction "RES6_RES6") (pintype "bidirectional"))
    )
    (net (code "74") (name "unconnected-(U2-PadRES7)") (class "Default")
      (node (ref "U2") (pin "RES7") (pinfunction "RES7_RES7") (pintype "bidirectional"))
    )
    (net (code "75") (name "unconnected-(U2-PadRESET_N)") (class "Default")
      (node (ref "U2") (pin "RESET_N") (pinfunction "RESET_N_RESET_N") (pintype "bidirectional"))
    )
    (net (code "76") (name "unconnected-(U2-PadSAFEBOOT_N)") (class "Default")
      (node (ref "U2") (pin "SAFEBOOT_N") (pinfunction "SAFEBOOT_N_SAFEBOOT_N") (pintype "bidirectional"))
    )
    (net (code "77") (name "unconnected-(U2-PadSCL)") (class "Default")
      (node (ref "U2") (pin "SCL") (pinfunction "SCL_SCL") (pintype "bidirectional"))
    )
    (net (code "78") (name "unconnected-(U2-PadSDA)") (class "Default")
      (node (ref "U2") (pin "SDA") (pinfunction "SDA_SDA") (pintype "bidirectional"))
    )
    (net (code "79") (name "unconnected-(U2-PadSQI_CLK)") (class "Default")
      (node (ref "U2") (pin "SQI_CLK") (pinfunction "SQI_CLK_SQI_CLK") (pintype "bidirectional"))
    )
    (net (code "80") (name "unconnected-(U2-PadSQI_CS_N)") (class "Default")
      (node (ref "U2") (pin "SQI_CS_N") (pinfunction "SQI_CS_N_SQI_CS_N") (pintype "bidirectional"))
    )
    (net (code "81") (name "unconnected-(U2-PadSQI_D0)") (class "Default")
      (node (ref "U2") (pin "SQI_D0") (pinfunction "SQI_D0_SQI_D0") (pintype "bidirectional"))
    )
    (net (code "82") (name "unconnected-(U2-PadSQI_D1)") (class "Default")
      (node (ref "U2") (pin "SQI_D1") (pinfunction "SQI_D1_SQI_D1") (pintype "bidirectional"))
    )
    (net (code "83") (name "unconnected-(U2-PadSQI_D2)") (class "Default")
      (node (ref "U2") (pin "SQI_D2") (pinfunction "SQI_D2_SQI_D2") (pintype "bidirectional"))
    )
    (net (code "84") (name "unconnected-(U2-PadSQI_D3)") (class "Default")
      (node (ref "U2") (pin "SQI_D3") (pinfunction "SQI_D3_SQI_D3") (pintype "bidirectional"))
    )
    (net (code "85") (name "unconnected-(U2-PadTIMEPULSE)") (class "Default")
      (node (ref "U2") (pin "TIMEPULSE") (pinfunction "TIMEPULSE_TIMEPULSE") (pintype "bidirectional"))
    )
    (net (code "86") (name "unconnected-(U7-PadCSB2)") (class "Default")
      (node (ref "U7") (pin "CSB2") (pinfunction "CSB2_CSB2") (pintype "bidirectional"))
    )
    (net (code "87") (name "unconnected-(U9-PadN{slash}C)") (class "Default")
      (node (ref "U9") (pin "N/C") (pinfunction "N/C_N/C") (pintype "bidirectional"))
    )
    (net (code "88") (name "unconnected-(U11-PadCLK0)") (class "Default")
      (node (ref "U11") (pin "CLK0") (pinfunction "CLK0_CLK0") (pintype "bidirectional"))
    )
    (net (code "89") (name "unconnected-(U11-PadCLK1)") (class "Default")
      (node (ref "U11") (pin "CLK1") (pinfunction "CLK1_CLK1") (pintype "bidirectional"))
    )
    (net (code "90") (name "unconnected-(U11-PadCLK2)") (class "Default")
      (node (ref "U11") (pin "CLK2") (pinfunction "CLK2_CLK2") (pintype "bidirectional"))
    )
    (net (code "91") (name "unconnected-(U11-PadCLK3)") (class "Default")
      (node (ref "U11") (pin "CLK3") (pinfunction "CLK3_CLK3") (pintype "bidirectional"))
    )
    (net (code "92") (name "unconnected-(U11-PadCLK4)") (class "Default")
      (node (ref "U11") (pin "CLK4") (pinfunction "CLK4_CLK4") (pintype "bidirectional"))
    )
    (net (code "93") (name "unconnected-(U11-PadCLK6)") (class "Default")
      (node (ref "U11") (pin "CLK6") (pinfunction "CLK6_CLK6") (pintype "bidirectional"))
    )
    (net (code "94") (name "unconnected-(U11-PadCLK7)") (class "Default")
      (node (ref "U11") (pin "CLK7") (pinfunction "CLK7_CLK7") (pintype "bidirectional"))
    )
    (net (code "95") (name "unconnected-(U11-PadXB)") (class "Default")
      (node (ref "U11") (pin "XB") (pinfunction "XB_XB") (pintype "bidirectional"))
    )
    (net (code "96") (name "unconnected-(U12-PadNC)") (class "Default")
      (node (ref "U12") (pin "NC") (pinfunction "NC_NC") (pintype "bidirectional"))
    )
    (net (code "97") (name "unconnected-(U15-PadINT)") (class "Default")
      (node (ref "U15") (pin "INT") (pinfunction "INT_INT") (pintype "bidirectional"))
    )
  )
)
